# Flashlight.net
KiCad netlist of a schematic drawn in EAGLE
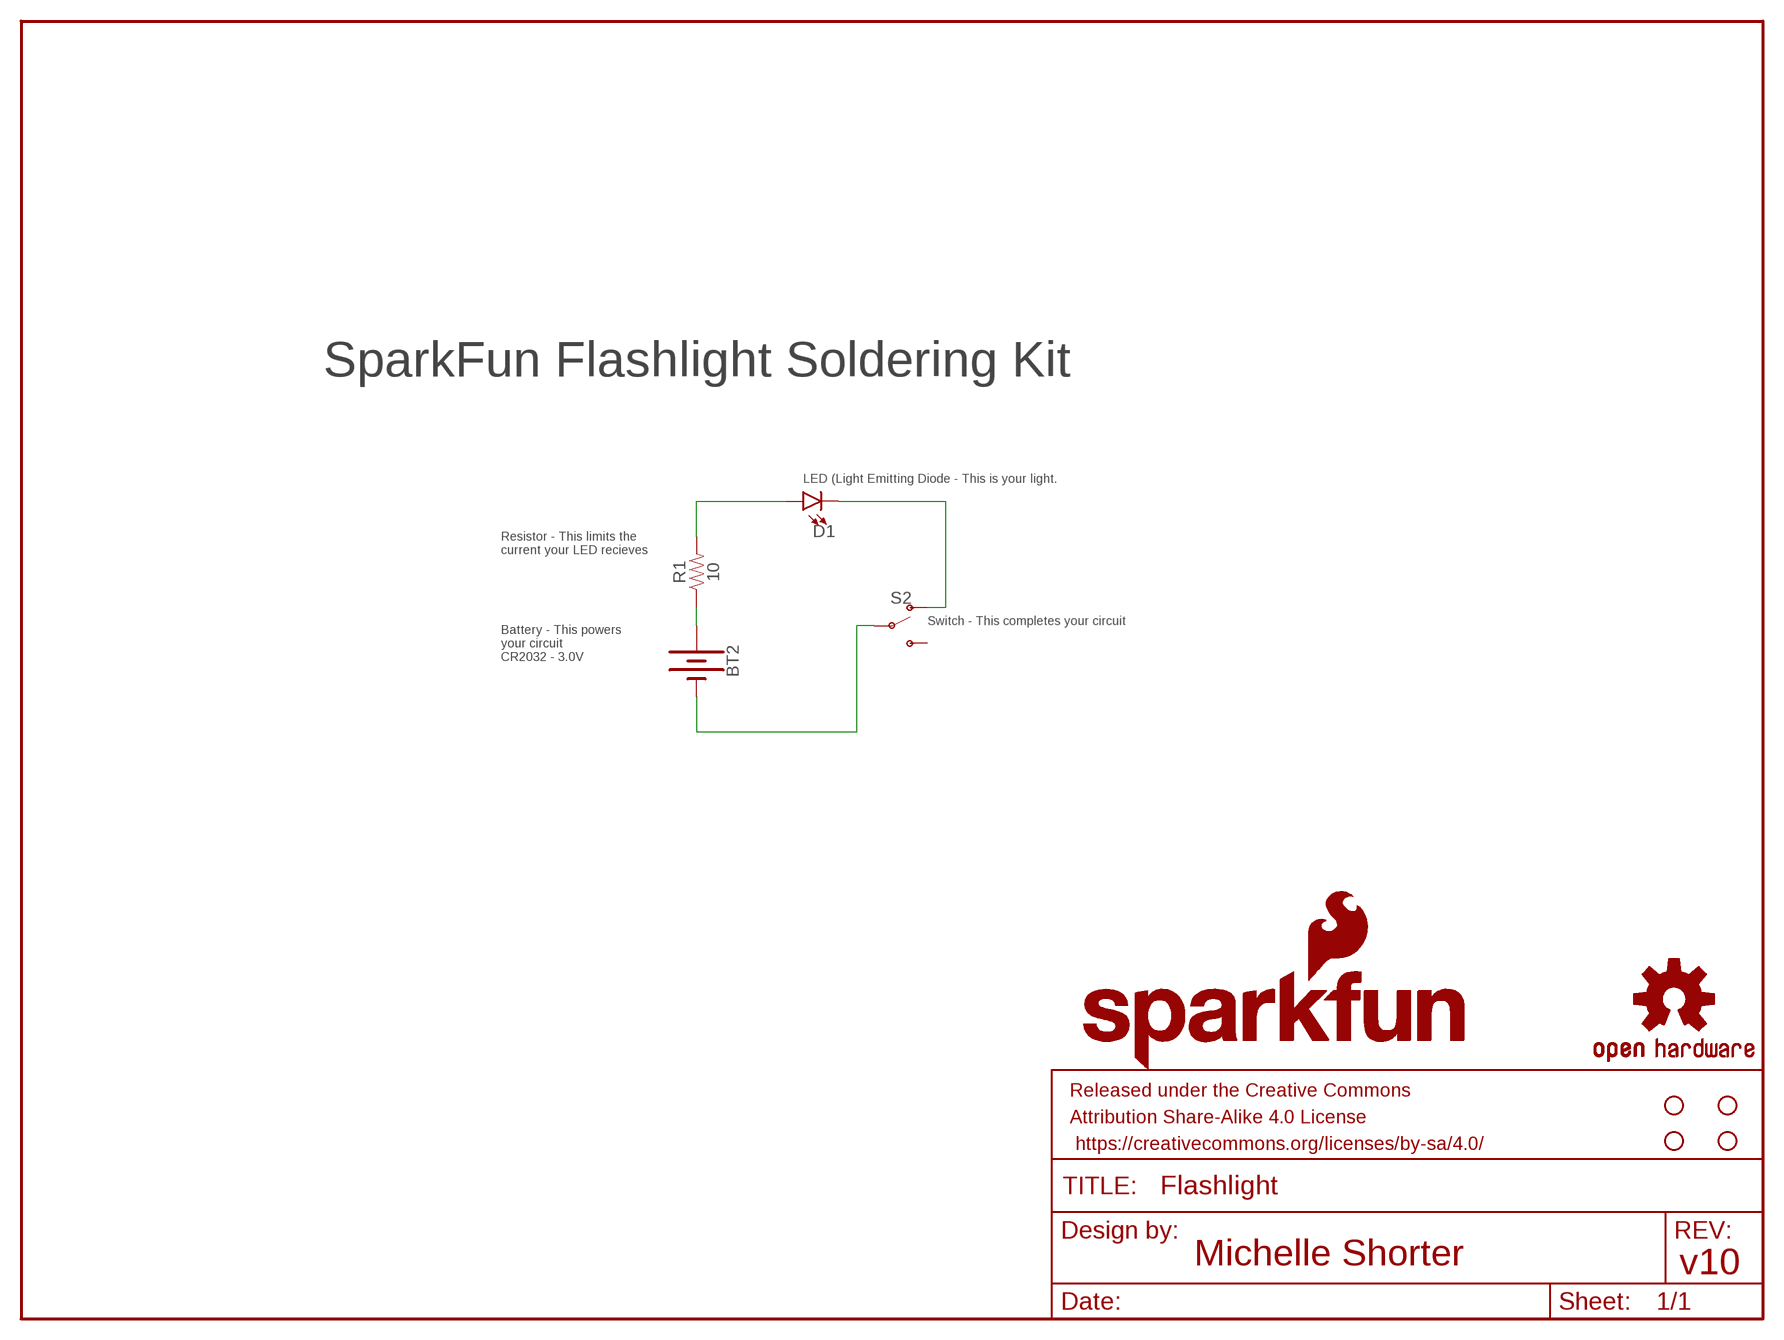
[diagram p0: schematic, sheet 1]

(export (version "E")
  (design (tool "Eeschema 10.0.6"))
  (components
    (comp (ref "BT2")
      (value "BATTERY-20MM_PTH_KIT")
      (footprint "eagle-import:BATTCOM_20MM_PTH_KIT")
      (libsource (lib "eagle-import") (part "BATTERY-20MM_PTH_KIT"))
    )
    (comp (ref "D1")
      (value "LED-5MM-KIT-NO-SILK")
      (footprint "eagle-import:LED_5MM-KIT-NO-SILK")
      (libsource (lib "eagle-import") (part "LED-5MM-KIT-NO-SILK"))
    )
    (comp (ref "FRAME1")
      (value "FRAME-LETTER")
      (footprint "eagle-import:CREATIVE_COMMONS")
      (libsource (lib "eagle-import") (part "FRAME-LETTER"))
    )
    (comp (ref "H1")
      (value "STAND-OFF")
      (footprint "eagle-import:STAND-OFF")
      (libsource (lib "eagle-import") (part "STAND-OFF"))
    )
    (comp (ref "H2")
      (value "STAND-OFF")
      (footprint "eagle-import:STAND-OFF")
      (libsource (lib "eagle-import") (part "STAND-OFF"))
    )
    (comp (ref "H3")
      (value "STAND-OFF")
      (footprint "eagle-import:STAND-OFF")
      (libsource (lib "eagle-import") (part "STAND-OFF"))
    )
    (comp (ref "H4")
      (value "STAND-OFF")
      (footprint "eagle-import:STAND-OFF")
      (libsource (lib "eagle-import") (part "STAND-OFF"))
    )
    (comp (ref "LOGO1")
      (value "OSHW-LOGOS")
      (footprint "eagle-import:OSHW-LOGO-S")
      (libsource (lib "eagle-import") (part "OSHW-LOGOS"))
    )
    (comp (ref "LOGO2")
      (value "SFE_LOGO_FLAME.1_INCH")
      (footprint "eagle-import:SFE_LOGO_FLAME_.1")
      (libsource (lib "eagle-import") (part "SFE_LOGO_FLAME.1_INCH"))
    )
    (comp (ref "LOGO3")
      (value "SFE_LOGO_NAME_FLAME.2_INCH")
      (footprint "eagle-import:SFE_LOGO_NAME_FLAME_.2")
      (libsource (lib "eagle-import") (part "SFE_LOGO_NAME_FLAME.2_INCH"))
    )
    (comp (ref "LOGO4")
      (value "SFE_LOGO_NAME.2_INCH")
      (footprint "eagle-import:SFE_LOGO_NAME_.2")
      (libsource (lib "eagle-import") (part "SFE_LOGO_NAME.2_INCH"))
    )
    (comp (ref "R1")
      (value "10")
      (footprint "eagle-import:AXIAL-0.3-KIT")
      (fields (field (name "PROD_ID") "8371"))
      (libsource (lib "eagle-import") (part "RESISTORAXIAL-0.3-KIT"))
    )
    (comp (ref "S2")
      (value "SWITCH-SPDT-PTH-11.6X4.0MM-KIT")
      (footprint "eagle-import:SWITCH_SPDT_PTH_11.6X4.0MM_KIT")
      (libsource (lib "eagle-import") (part "SWITCH-SPDT-PTH-11.6X4.0MM-KIT"))
    )
  )
  (nets
    (net (code "1") (name "Net-(BT2-+)") (class "Default")
      (node (ref "BT2") (pin "1") (pinfunction "+_1") (pintype "power_in"))
      (node (ref "R1") (pin "P$1") (pinfunction "1_P$1") (pintype "passive"))
    )
    (net (code "2") (name "Net-(BT2--)") (class "Default")
      (node (ref "BT2") (pin "2") (pinfunction "-_2") (pintype "power_in"))
      (node (ref "S2") (pin "2") (pinfunction "P_2") (pintype "passive"))
    )
    (net (code "3") (name "Net-(D1-C)") (class "Default")
      (node (ref "D1") (pin "K") (pinfunction "C_K") (pintype "passive"))
      (node (ref "S2") (pin "1") (pinfunction "O_1") (pintype "passive"))
    )
    (net (code "4") (name "Net-(R1-2)") (class "Default")
      (node (ref "D1") (pin "A") (pinfunction "A_A") (pintype "passive"))
      (node (ref "R1") (pin "P$2") (pinfunction "2_P$2") (pintype "passive"))
    )
    (net (code "5") (name "unconnected-(S2-S-Pad3)") (class "Default")
      (node (ref "S2") (pin "3") (pinfunction "S_3") (pintype "passive"))
    )
  )
)
